# FTDI_mini-usb.net
KiCad netlist of a schematic drawn in EAGLE
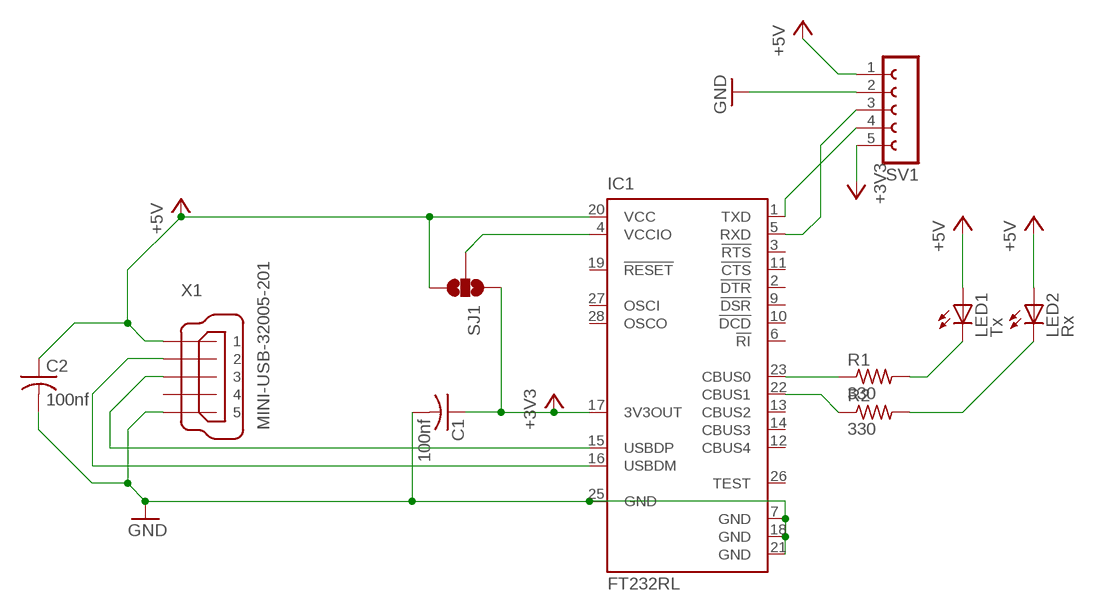
[diagram p0: schematic, sheet 1]

(export (version "E")
  (design (tool "Eeschema 10.0.6"))
  (components
    (comp (ref "C1")
      (value "100nf")
      (footprint "eagle-import:C0805K")
      (libsource (lib "eagle-import") (part "C-USC0805K"))
    )
    (comp (ref "C2")
      (value "100nf")
      (footprint "eagle-import:C0805K")
      (libsource (lib "eagle-import") (part "C-USC0805K"))
    )
    (comp (ref "IC1")
      (value "FT232RL")
      (footprint "eagle-import:SSOP28")
      (libsource (lib "eagle-import") (part "FT232RL"))
    )
    (comp (ref "LED1")
      (value "Tx")
      (footprint "eagle-import:CHIPLED_0805")
      (libsource (lib "eagle-import") (part "LEDCHIPLED_0805"))
    )
    (comp (ref "LED2")
      (value "Rx")
      (footprint "eagle-import:CHIPLED_0805")
      (libsource (lib "eagle-import") (part "LEDCHIPLED_0805"))
    )
    (comp (ref "R1")
      (value "330")
      (footprint "eagle-import:R0805W")
      (libsource (lib "eagle-import") (part "R-US_R0805W"))
    )
    (comp (ref "R2")
      (value "330")
      (footprint "eagle-import:R0805W")
      (libsource (lib "eagle-import") (part "R-US_R0805W"))
    )
    (comp (ref "SJ1")
      (value "SOLDERJUMPER_2WAYS")
      (footprint "eagle-import:SJ_3")
      (libsource (lib "eagle-import") (part "SOLDERJUMPER_2WAYS"))
    )
    (comp (ref "SV1")
      (value "FE05-1")
      (footprint "eagle-import:FE05-1")
      (libsource (lib "eagle-import") (part "FE05-1"))
    )
    (comp (ref "X1")
      (value "MINI-USB-32005-201")
      (footprint "eagle-import:32005-201")
      (libsource (lib "eagle-import") (part "MINI-USB-32005-201"))
    )
  )
  (nets
    (net (code "1") (name "+3V3") (class "Default")
      (node (ref "C1") (pin "1") (pinfunction "1_1") (pintype "passive"))
      (node (ref "IC1") (pin "17") (pinfunction "3V3OUT_17") (pintype "output"))
      (node (ref "SJ1") (pin "1") (pinfunction "1_1") (pintype "passive"))
      (node (ref "SV1") (pin "5") (pinfunction "5_5") (pintype "passive"))
    )
    (net (code "2") (name "+5V") (class "Default")
      (node (ref "C2") (pin "1") (pinfunction "1_1") (pintype "passive"))
      (node (ref "IC1") (pin "20") (pinfunction "VCC_20") (pintype "power_in"))
      (node (ref "LED1") (pin "A") (pinfunction "A_A") (pintype "passive"))
      (node (ref "LED2") (pin "A") (pinfunction "A_A") (pintype "passive"))
      (node (ref "SJ1") (pin "3") (pinfunction "3_3") (pintype "passive"))
      (node (ref "SV1") (pin "1") (pinfunction "1_1") (pintype "passive"))
      (node (ref "X1") (pin "1") (pinfunction "1_1") (pintype "passive"))
    )
    (net (code "3") (name "GND") (class "Default")
      (node (ref "C1") (pin "2") (pinfunction "2_2") (pintype "passive"))
      (node (ref "C2") (pin "2") (pinfunction "2_2") (pintype "passive"))
      (node (ref "IC1") (pin "18") (pinfunction "GND_18") (pintype "power_in"))
      (node (ref "IC1") (pin "21") (pinfunction "GND_21") (pintype "power_in"))
      (node (ref "IC1") (pin "25") (pinfunction "GND_25") (pintype "power_in"))
      (node (ref "IC1") (pin "7") (pinfunction "GND_7") (pintype "power_in"))
      (node (ref "SV1") (pin "2") (pinfunction "2_2") (pintype "passive"))
      (node (ref "X1") (pin "5") (pinfunction "5_5") (pintype "passive"))
    )
    (net (code "4") (name "Net-(IC1-CBUS0)") (class "Default")
      (node (ref "IC1") (pin "23") (pinfunction "CBUS0_23") (pintype "bidirectional"))
      (node (ref "R1") (pin "1") (pinfunction "1_1") (pintype "passive"))
    )
    (net (code "5") (name "Net-(IC1-CBUS1)") (class "Default")
      (node (ref "IC1") (pin "22") (pinfunction "CBUS1_22") (pintype "bidirectional"))
      (node (ref "R2") (pin "1") (pinfunction "1_1") (pintype "passive"))
    )
    (net (code "6") (name "Net-(IC1-RXD)") (class "Default")
      (node (ref "IC1") (pin "5") (pinfunction "RXD_5") (pintype "input"))
      (node (ref "SV1") (pin "3") (pinfunction "3_3") (pintype "passive"))
    )
    (net (code "7") (name "Net-(IC1-TXD)") (class "Default")
      (node (ref "IC1") (pin "1") (pinfunction "TXD_1") (pintype "output"))
      (node (ref "SV1") (pin "4") (pinfunction "4_4") (pintype "passive"))
    )
    (net (code "8") (name "Net-(IC1-USBDM)") (class "Default")
      (node (ref "IC1") (pin "16") (pinfunction "USBDM_16") (pintype "bidirectional"))
      (node (ref "X1") (pin "2") (pinfunction "2_2") (pintype "passive"))
    )
    (net (code "9") (name "Net-(IC1-USBDP)") (class "Default")
      (node (ref "IC1") (pin "15") (pinfunction "USBDP_15") (pintype "bidirectional"))
      (node (ref "X1") (pin "3") (pinfunction "3_3") (pintype "passive"))
    )
    (net (code "10") (name "Net-(IC1-VCCIO)") (class "Default")
      (node (ref "IC1") (pin "4") (pinfunction "VCCIO_4") (pintype "power_in"))
      (node (ref "SJ1") (pin "2") (pinfunction "2_2") (pintype "passive"))
    )
    (net (code "11") (name "Net-(LED1-PadC)") (class "Default")
      (node (ref "LED1") (pin "C") (pinfunction "C_C") (pintype "passive"))
      (node (ref "R1") (pin "2") (pinfunction "2_2") (pintype "passive"))
    )
    (net (code "12") (name "Net-(LED2-PadC)") (class "Default")
      (node (ref "LED2") (pin "C") (pinfunction "C_C") (pintype "passive"))
      (node (ref "R2") (pin "2") (pinfunction "2_2") (pintype "passive"))
    )
    (net (code "13") (name "unconnected-(IC1-CBUS2-Pad13)") (class "Default")
      (node (ref "IC1") (pin "13") (pinfunction "CBUS2_13") (pintype "bidirectional"))
    )
    (net (code "14") (name "unconnected-(IC1-CBUS3-Pad14)") (class "Default")
      (node (ref "IC1") (pin "14") (pinfunction "CBUS3_14") (pintype "bidirectional"))
    )
    (net (code "15") (name "unconnected-(IC1-CBUS4-Pad12)") (class "Default")
      (node (ref "IC1") (pin "12") (pinfunction "CBUS4_12") (pintype "bidirectional"))
    )
    (net (code "16") (name "unconnected-(IC1-OSCI-Pad27)") (class "Default")
      (node (ref "IC1") (pin "27") (pinfunction "OSCI_27") (pintype "input"))
    )
    (net (code "17") (name "unconnected-(IC1-OSCO-Pad28)") (class "Default")
      (node (ref "IC1") (pin "28") (pinfunction "OSCO_28") (pintype "output"))
    )
    (net (code "18") (name "unconnected-(IC1-TEST-Pad26)") (class "Default")
      (node (ref "IC1") (pin "26") (pinfunction "TEST_26") (pintype "input"))
    )
    (net (code "19") (name "unconnected-(IC1-~{CTS}-Pad11)") (class "Default")
      (node (ref "IC1") (pin "11") (pinfunction "~{CTS}_11") (pintype "input"))
    )
    (net (code "20") (name "unconnected-(IC1-~{DCD}-Pad10)") (class "Default")
      (node (ref "IC1") (pin "10") (pinfunction "~{DCD}_10") (pintype "input"))
    )
    (net (code "21") (name "unconnected-(IC1-~{DSR}-Pad9)") (class "Default")
      (node (ref "IC1") (pin "9") (pinfunction "~{DSR}_9") (pintype "input"))
    )
    (net (code "22") (name "unconnected-(IC1-~{DTR}-Pad2)") (class "Default")
      (node (ref "IC1") (pin "2") (pinfunction "~{DTR}_2") (pintype "output"))
    )
    (net (code "23") (name "unconnected-(IC1-~{RESET}-Pad19)") (class "Default")
      (node (ref "IC1") (pin "19") (pinfunction "~{RESET}_19") (pintype "input"))
    )
    (net (code "24") (name "unconnected-(IC1-~{RI}-Pad6)") (class "Default")
      (node (ref "IC1") (pin "6") (pinfunction "~{RI}_6") (pintype "input"))
    )
    (net (code "25") (name "unconnected-(IC1-~{RTS}-Pad3)") (class "Default")
      (node (ref "IC1") (pin "3") (pinfunction "~{RTS}_3") (pintype "output"))
    )
    (net (code "26") (name "unconnected-(X1-Pad4)") (class "Default")
      (node (ref "X1") (pin "4") (pinfunction "4_4") (pintype "passive"))
    )
  )
)
